# 04_ZYNQ_BANK0.net
KiCad netlist of a schematic drawn in Altium Designer
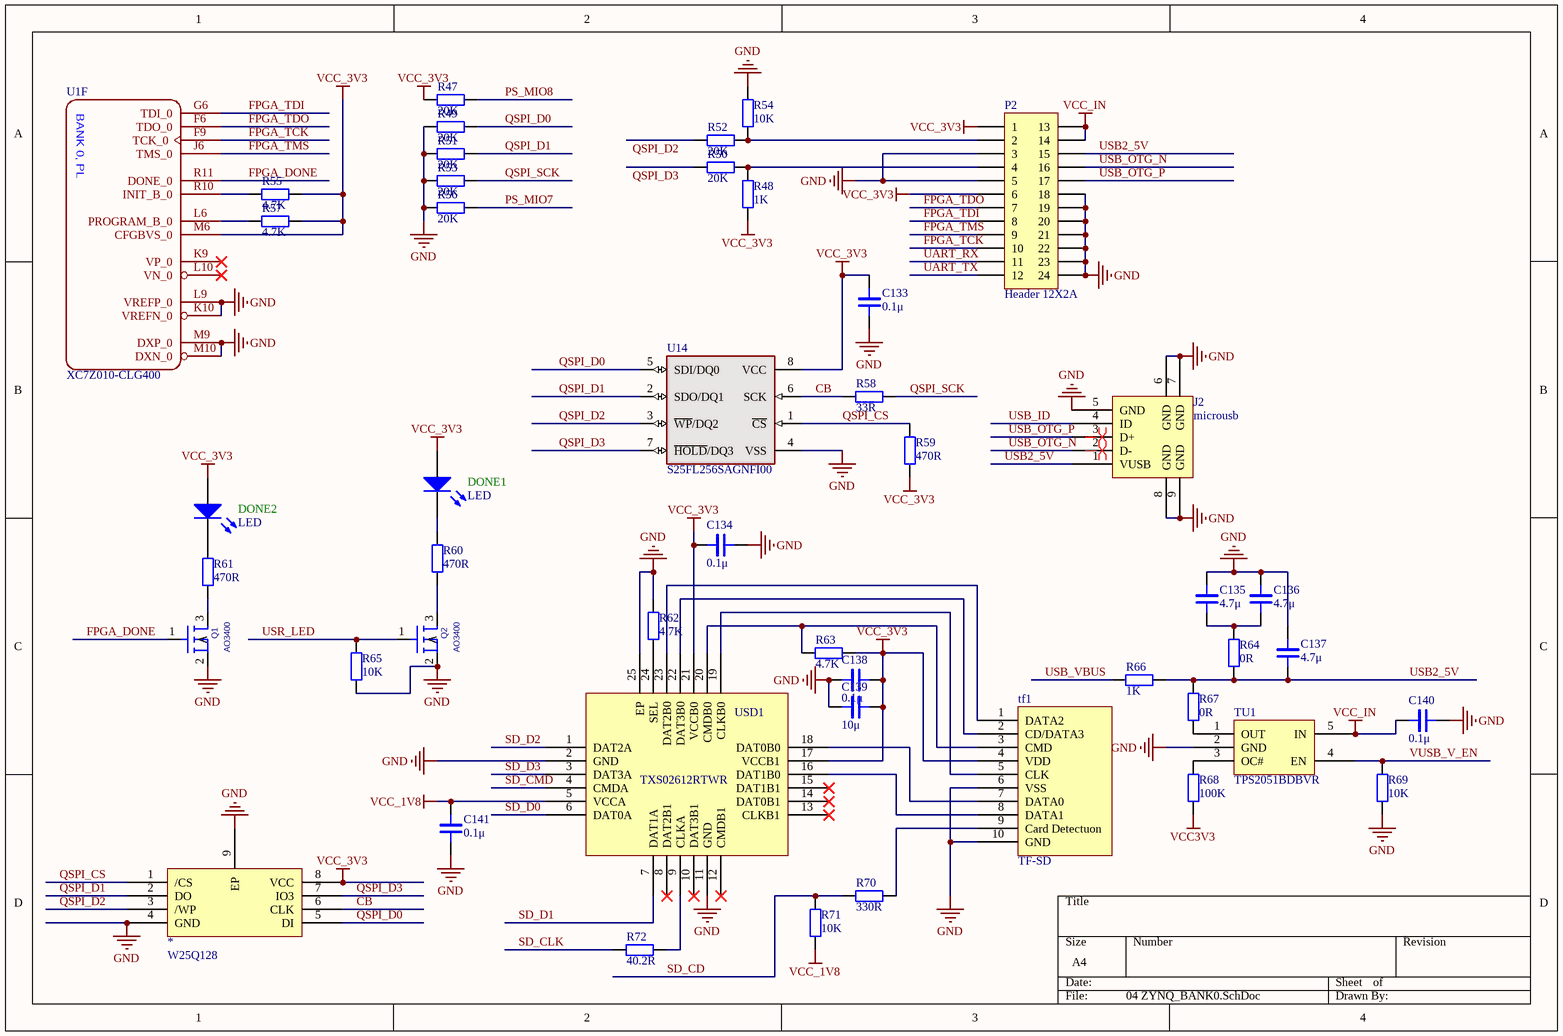
[diagram p0: 04 ZYNQ_BANK0.SchDoc]

(export (version "E")
  (design (tool "Eeschema 10.0.6"))
  (components
    (comp (ref "*") (value "W25Q128") (footprint "W25Q256") (libsource (lib "Schlib1") (part "W25Q128")))
    (comp (ref "C133")
      (value "0.1μ")
      (footprint "LC-0402_C")
      (description "Capacitor")
      (libsource (lib "DDR3_xc7z010-clg400") (part "CAP_2"))
    )
    (comp (ref "C134")
      (value "0.1μ")
      (footprint "LC-0402_C")
      (description "Capacitor")
      (libsource (lib "DDR3_xc7z010-clg400") (part "CAP_2"))
    )
    (comp (ref "C135")
      (value "4.7μ")
      (footprint "LC-0402_C")
      (description "Capacitor")
      (libsource (lib "DDR3_xc7z010-clg400") (part "CAP_2"))
    )
    (comp (ref "C136")
      (value "4.7μ")
      (footprint "LC-0402_C")
      (description "Capacitor")
      (libsource (lib "DDR3_xc7z010-clg400") (part "CAP_2"))
    )
    (comp (ref "C137")
      (value "4.7μ")
      (footprint "LC-0402_C")
      (description "Capacitor")
      (libsource (lib "DDR3_xc7z010-clg400") (part "CAP_2"))
    )
    (comp (ref "C138")
      (value "0.1μ")
      (footprint "LC-0402_C")
      (description "Capacitor")
      (libsource (lib "DDR3_xc7z010-clg400") (part "CAP_2"))
    )
    (comp (ref "C139")
      (value "10μ")
      (footprint "LC-0402_C")
      (description "Capacitor")
      (libsource (lib "DDR3_xc7z010-clg400") (part "CAP_2"))
    )
    (comp (ref "C140")
      (value "0.1μ")
      (footprint "LC-0402_C")
      (description "Capacitor")
      (libsource (lib "DDR3_xc7z010-clg400") (part "CAP_2"))
    )
    (comp (ref "C141")
      (value "0.1μ")
      (footprint "LC-0402_C")
      (description "Capacitor")
      (libsource (lib "DDR3_xc7z010-clg400") (part "CAP_2"))
    )
    (comp (ref "DONE1")
      (value "LED")
      (footprint "D0402")
      (description "Typical INFRARED GaAs LED")
      (fields (field (name "PUBLISHER") "Altium Limited"))
      (libsource (lib "Miscellaneous Devices") (part "LED0"))
    )
    (comp (ref "DONE2")
      (value "LED")
      (footprint "D0402")
      (description "Typical INFRARED GaAs LED")
      (fields (field (name "PUBLISHER") "Altium Limited"))
      (libsource (lib "Miscellaneous Devices") (part "LED0"))
    )
    (comp (ref "J2")
      (value "microusb")
      (footprint "micro usb")
      (libsource (lib "AD9363_ZYNQ_V2") (part "microusb"))
    )
    (comp (ref "P2")
      (value "Header 12X2A")
      (footprint "HDR2X12_CEN")
      (description "Header, 12-Pin, Dual row")
      (fields (field (name "PUBLISHER") "Altium Limited"))
      (libsource (lib "Miscellaneous Connectors") (part "Header 12X2A"))
    )
    (comp (ref "Q1") (value "AO3400") (footprint "NMOS") (libsource (lib "ZYNQ领航者底板") (part "AO3400")))
    (comp (ref "Q2") (value "AO3400") (footprint "NMOS") (libsource (lib "ZYNQ领航者底板") (part "AO3400")))
    (comp (ref "R47")
      (value "20K")
      (footprint "LC-0402_R")
      (description "Resistor")
      (libsource (lib "") (part "RES_2"))
    )
    (comp (ref "R48")
      (value "1K")
      (footprint "LC-0402_R")
      (description "Resistor")
      (libsource (lib "") (part "RES_3"))
    )
    (comp (ref "R49")
      (value "20K")
      (footprint "LC-0402_R")
      (description "Resistor")
      (libsource (lib "") (part "RES_2"))
    )
    (comp (ref "R50")
      (value "20K")
      (footprint "LC-0402_R")
      (description "Resistor")
      (libsource (lib "DDR3_xc7z010-clg400") (part "RES"))
    )
    (comp (ref "R51")
      (value "20K")
      (footprint "LC-0402_R")
      (description "Resistor")
      (libsource (lib "") (part "RES_2"))
    )
    (comp (ref "R52")
      (value "20K")
      (footprint "LC-0402_R")
      (description "Resistor")
      (libsource (lib "DDR3_xc7z010-clg400") (part "RES"))
    )
    (comp (ref "R53")
      (value "20K")
      (footprint "LC-0402_R")
      (description "Resistor")
      (libsource (lib "") (part "RES_2"))
    )
    (comp (ref "R54")
      (value "10K")
      (footprint "LC-0402_R")
      (description "Resistor")
      (libsource (lib "") (part "RES_3"))
    )
    (comp (ref "R55")
      (value "4.7K")
      (footprint "LC-0402_R")
      (description "Resistor")
      (libsource (lib "DDR3_xc7z010-clg400") (part "RES"))
    )
    (comp (ref "R56")
      (value "20K")
      (footprint "LC-0402_R")
      (description "Resistor")
      (libsource (lib "") (part "RES_2"))
    )
    (comp (ref "R57")
      (value "4.7K")
      (footprint "LC-0402_R")
      (description "Resistor")
      (libsource (lib "DDR3_xc7z010-clg400") (part "RES"))
    )
    (comp (ref "R58")
      (value "33R")
      (footprint "LC-0402_R")
      (description "Resistor")
      (libsource (lib "") (part "RES_2"))
    )
    (comp (ref "R59")
      (value "470R")
      (footprint "LC-0402_R")
      (description "Resistor")
      (libsource (lib "") (part "RES_1"))
    )
    (comp (ref "R60")
      (value "470R")
      (footprint "LC-0402_R")
      (description "Resistor")
      (libsource (lib "") (part "RES_3"))
    )
    (comp (ref "R61")
      (value "470R")
      (footprint "LC-0402_R")
      (description "Resistor")
      (libsource (lib "") (part "RES_3"))
    )
    (comp (ref "R62")
      (value "4.7K")
      (footprint "LC-0402_R")
      (description "Resistor")
      (libsource (lib "") (part "RES_1"))
    )
    (comp (ref "R63")
      (value "4.7K")
      (footprint "LC-0402_R")
      (description "Resistor")
      (libsource (lib "DDR3_xc7z010-clg400") (part "RES"))
    )
    (comp (ref "R64")
      (value "0R")
      (footprint "LC-0402_R")
      (description "Resistor")
      (libsource (lib "") (part "RES_1"))
    )
    (comp (ref "R65")
      (value "10K")
      (footprint "LC-0402_R")
      (description "Resistor")
      (libsource (lib "") (part "RES_1"))
    )
    (comp (ref "R66")
      (value "1K")
      (footprint "LC-0402_R")
      (description "Resistor")
      (libsource (lib "DDR3_xc7z010-clg400") (part "RES"))
    )
    (comp (ref "R67")
      (value "0R")
      (footprint "LC-0402_R")
      (description "Resistor")
      (libsource (lib "") (part "RES_1"))
    )
    (comp (ref "R68")
      (value "100K")
      (footprint "LC-0402_R")
      (description "Resistor")
      (libsource (lib "") (part "RES_1"))
    )
    (comp (ref "R69")
      (value "10K")
      (footprint "LC-0402_R")
      (description "Resistor")
      (libsource (lib "") (part "RES_1"))
    )
    (comp (ref "R70")
      (value "330R")
      (footprint "LC-0402_R")
      (description "Resistor")
      (libsource (lib "DDR3_xc7z010-clg400") (part "RES"))
    )
    (comp (ref "R71")
      (value "10K")
      (footprint "LC-0402_R")
      (description "Resistor")
      (libsource (lib "") (part "RES_1"))
    )
    (comp (ref "R72")
      (value "40.2R")
      (footprint "LC-0402_R")
      (description "Resistor")
      (libsource (lib "DDR3_xc7z010-clg400") (part "RES"))
    )
    (comp (ref "tf1") (value "TF-SD") (footprint "TF") (libsource (lib "PCB_Project") (part "TF-SD")))
    (comp (ref "TU1")
      (value "TPS2051BDBVR")
      (footprint "TPS2051BDBVR")
      (libsource (lib "Schlib1") (part "TPS2051BDBVR"))
    )
    (comp (ref "U1")
      (value "XC7Z010-CLG400")
      (footprint "CLG400-0.8")
      (libsource (lib "DDR3_xc7z010-clg400") (part "XC7Z010-CLG400"))
    )
    (comp (ref "U14")
      (value "S25FL256SAGNFI00")
      (footprint "MLP8")
      (description "Serial Flash Memory, 16Mbit, Low Voltage, 50MHz SPI Bus Interface")
      (fields (field (name "MANUFACTURER") "Spansion"))
      (libsource (lib "PCB_Project") (part "N25Q12-F8"))
    )
    (comp (ref "USD1")
      (value "TXS02612RTWR")
      (footprint "TXS02612RTWR")
      (libsource (lib "Schlib1") (part "TXS02612RTWR"))
    )
  )
  (nets
    (net (code "1") (name "/CB") (class "Default")
      (node (ref "*") (pin "6") (pinfunction "CLK_6") (pintype "passive"))
      (node (ref "R58") (pin "1") (pinfunction "1_1") (pintype "passive"))
      (node (ref "U14") (pin "6") (pinfunction "SCK_6") (pintype "input"))
    )
    (net (code "2") (name "/FPGA_DONE") (class "Default")
      (node (ref "Q1") (pin "1") (pinfunction "G_1") (pintype "passive"))
      (node (ref "U1") (pin "R11") (pinfunction "DONE_0_R11") (pintype "passive"))
    )
    (net (code "3") (name "/FPGA_TCK") (class "Default")
      (node (ref "P2") (pin "10") (pinfunction "10_10") (pintype "passive"))
      (node (ref "U1") (pin "F9") (pinfunction "TCK_0_F9") (pintype "passive"))
    )
    (net (code "4") (name "/FPGA_TDI") (class "Default")
      (node (ref "P2") (pin "8") (pinfunction "8_8") (pintype "passive"))
      (node (ref "U1") (pin "G6") (pinfunction "TDI_0_G6") (pintype "passive"))
    )
    (net (code "5") (name "/FPGA_TDO") (class "Default")
      (node (ref "P2") (pin "7") (pinfunction "7_7") (pintype "passive"))
      (node (ref "U1") (pin "F6") (pinfunction "TDO_0_F6") (pintype "passive"))
    )
    (net (code "6") (name "/FPGA_TMS") (class "Default")
      (node (ref "P2") (pin "9") (pinfunction "9_9") (pintype "passive"))
      (node (ref "U1") (pin "J6") (pinfunction "TMS_0_J6") (pintype "passive"))
    )
    (net (code "7") (name "/PS_MIO7") (class "Default")
      (node (ref "R56") (pin "2") (pinfunction "2_2") (pintype "passive"))
    )
    (net (code "8") (name "/PS_MIO8") (class "Default")
      (node (ref "R47") (pin "2") (pinfunction "2_2") (pintype "passive"))
    )
    (net (code "9") (name "/QSPI_CS") (class "Default")
      (node (ref "*") (pin "1") (pinfunction "/CS_1") (pintype "passive"))
      (node (ref "R59") (pin "1") (pinfunction "1_1") (pintype "passive"))
      (node (ref "U14") (pin "1") (pinfunction "~{CS}_1") (pintype "input"))
    )
    (net (code "10") (name "/QSPI_D0") (class "Default")
      (node (ref "*") (pin "5") (pinfunction "DI_5") (pintype "passive"))
      (node (ref "R49") (pin "2") (pinfunction "2_2") (pintype "passive"))
      (node (ref "U14") (pin "5") (pinfunction "SDI/DQ0_5") (pintype "bidirectional"))
    )
    (net (code "11") (name "/QSPI_D1") (class "Default")
      (node (ref "*") (pin "2") (pinfunction "DO_2") (pintype "passive"))
      (node (ref "R51") (pin "2") (pinfunction "2_2") (pintype "passive"))
      (node (ref "U14") (pin "2") (pinfunction "SDO/DQ1_2") (pintype "bidirectional"))
    )
    (net (code "12") (name "/QSPI_D2") (class "Default")
      (node (ref "*") (pin "3") (pinfunction "/WP_3") (pintype "passive"))
      (node (ref "R52") (pin "2") (pinfunction "2_2") (pintype "passive"))
      (node (ref "U14") (pin "3") (pinfunction "~{WP}/DQ2_3") (pintype "bidirectional"))
    )
    (net (code "13") (name "/QSPI_D3") (class "Default")
      (node (ref "*") (pin "7") (pinfunction "IO3_7") (pintype "passive"))
      (node (ref "R50") (pin "2") (pinfunction "2_2") (pintype "passive"))
      (node (ref "U14") (pin "7") (pinfunction "~{HOLD}/DQ3_7") (pintype "bidirectional"))
    )
    (net (code "14") (name "/QSPI_SCK") (class "Default")
      (node (ref "R53") (pin "2") (pinfunction "2_2") (pintype "passive"))
      (node (ref "R58") (pin "2") (pinfunction "2_2") (pintype "passive"))
    )
    (net (code "15") (name "/SD_CD") (class "Default")
      (node (ref "R70") (pin "2") (pinfunction "2_2") (pintype "passive"))
      (node (ref "R71") (pin "1") (pinfunction "1_1") (pintype "passive"))
    )
    (net (code "16") (name "/SD_CLK") (class "Default")
      (node (ref "R72") (pin "2") (pinfunction "2_2") (pintype "passive"))
    )
    (net (code "17") (name "/SD_CMD") (class "Default")
      (node (ref "USD1") (pin "4") (pinfunction "CMDA_4") (pintype "passive"))
    )
    (net (code "18") (name "/SD_D0") (class "Default")
      (node (ref "USD1") (pin "6") (pinfunction "DAT0A_6") (pintype "passive"))
    )
    (net (code "19") (name "/SD_D1") (class "Default")
      (node (ref "USD1") (pin "7") (pinfunction "DAT1A_7") (pintype "passive"))
    )
    (net (code "20") (name "/SD_D2") (class "Default")
      (node (ref "USD1") (pin "1") (pinfunction "DAT2A_1") (pintype "passive"))
    )
    (net (code "21") (name "/SD_D3") (class "Default")
      (node (ref "USD1") (pin "3") (pinfunction "DAT3A_3") (pintype "passive"))
    )
    (net (code "22") (name "/UART_RX") (class "Default")
      (node (ref "P2") (pin "11") (pinfunction "11_11") (pintype "passive"))
    )
    (net (code "23") (name "/UART_TX") (class "Default")
      (node (ref "P2") (pin "12") (pinfunction "12_12") (pintype "passive"))
    )
    (net (code "24") (name "/USB2_5V") (class "Default")
      (node (ref "C137") (pin "1") (pinfunction "1_1") (pintype "passive"))
      (node (ref "J2") (pin "1") (pinfunction "VUSB_1") (pintype "passive"))
      (node (ref "P2") (pin "15") (pinfunction "15_15") (pintype "passive"))
      (node (ref "R64") (pin "2") (pinfunction "2_2") (pintype "passive"))
      (node (ref "R66") (pin "1") (pinfunction "1_1") (pintype "passive"))
      (node (ref "R67") (pin "1") (pinfunction "1_1") (pintype "passive"))
    )
    (net (code "25") (name "/USB_ID") (class "Default")
      (node (ref "J2") (pin "4") (pinfunction "ID_4") (pintype "passive"))
    )
    (net (code "26") (name "/USB_OTG_N") (class "Default")
      (node (ref "J2") (pin "2") (pinfunction "D-_2") (pintype "passive"))
      (node (ref "P2") (pin "16") (pinfunction "16_16") (pintype "passive"))
    )
    (net (code "27") (name "/USB_OTG_P") (class "Default")
      (node (ref "J2") (pin "3") (pinfunction "D+_3") (pintype "passive"))
      (node (ref "P2") (pin "17") (pinfunction "17_17") (pintype "passive"))
    )
    (net (code "28") (name "/USB_VBUS") (class "Default")
      (node (ref "R66") (pin "2") (pinfunction "2_2") (pintype "passive"))
    )
    (net (code "29") (name "/USR_LED") (class "Default")
      (node (ref "Q2") (pin "1") (pinfunction "G_1") (pintype "passive"))
      (node (ref "R65") (pin "1") (pinfunction "1_1") (pintype "passive"))
    )
    (net (code "30") (name "/VUSB_V_EN") (class "Default")
      (node (ref "R69") (pin "1") (pinfunction "1_1") (pintype "passive"))
      (node (ref "TU1") (pin "4") (pinfunction "EN_4") (pintype "passive"))
    )
    (net (code "31") (name "GND") (class "Default")
      (node (ref "*") (pin "4") (pinfunction "GND_4") (pintype "passive"))
      (node (ref "*") (pin "9") (pinfunction "EP_9") (pintype "passive"))
      (node (ref "C133") (pin "2") (pinfunction "2_2") (pintype "passive"))
      (node (ref "C134") (pin "2") (pinfunction "2_2") (pintype "passive"))
      (node (ref "C135") (pin "2") (pinfunction "2_2") (pintype "passive"))
      (node (ref "C136") (pin "2") (pinfunction "2_2") (pintype "passive"))
      (node (ref "C137") (pin "2") (pinfunction "2_2") (pintype "passive"))
      (node (ref "C138") (pin "2") (pinfunction "2_2") (pintype "passive"))
      (node (ref "C139") (pin "2") (pinfunction "2_2") (pintype "passive"))
      (node (ref "C140") (pin "1") (pinfunction "1_1") (pintype "passive"))
      (node (ref "C141") (pin "2") (pinfunction "2_2") (pintype "passive"))
      (node (ref "J2") (pin "5") (pinfunction "GND_5") (pintype "passive"))
      (node (ref "J2") (pin "6") (pinfunction "GND_6") (pintype "passive"))
      (node (ref "J2") (pin "7") (pinfunction "GND_7") (pintype "passive"))
      (node (ref "J2") (pin "8") (pinfunction "GND_8") (pintype "passive"))
      (node (ref "J2") (pin "9") (pinfunction "GND_9") (pintype "passive"))
      (node (ref "P2") (pin "18") (pinfunction "18_18") (pintype "passive"))
      (node (ref "P2") (pin "19") (pinfunction "19_19") (pintype "passive"))
      (node (ref "P2") (pin "20") (pinfunction "20_20") (pintype "passive"))
      (node (ref "P2") (pin "21") (pinfunction "21_21") (pintype "passive"))
      (node (ref "P2") (pin "22") (pinfunction "22_22") (pintype "passive"))
      (node (ref "P2") (pin "23") (pinfunction "23_23") (pintype "passive"))
      (node (ref "P2") (pin "24") (pinfunction "24_24") (pintype "passive"))
      (node (ref "P2") (pin "3") (pinfunction "3_3") (pintype "passive"))
      (node (ref "P2") (pin "5") (pinfunction "5_5") (pintype "passive"))
      (node (ref "Q1") (pin "2") (pinfunction "S_2") (pintype "passive"))
      (node (ref "Q2") (pin "2") (pinfunction "S_2") (pintype "passive"))
      (node (ref "R49") (pin "1") (pinfunction "1_1") (pintype "passive"))
      (node (ref "R51") (pin "1") (pinfunction "1_1") (pintype "passive"))
      (node (ref "R53") (pin "1") (pinfunction "1_1") (pintype "passive"))
      (node (ref "R54") (pin "2") (pinfunction "2_2") (pintype "passive"))
      (node (ref "R56") (pin "1") (pinfunction "1_1") (pintype "passive"))
      (node (ref "R62") (pin "1") (pinfunction "1_1") (pintype "passive"))
      (node (ref "R65") (pin "2") (pinfunction "2_2") (pintype "passive"))
      (node (ref "R69") (pin "2") (pinfunction "2_2") (pintype "passive"))
      (node (ref "TU1") (pin "2") (pinfunction "GND_2") (pintype "passive"))
      (node (ref "U1") (pin "K10") (pinfunction "VREFN_0_K10") (pintype "passive"))
      (node (ref "U1") (pin "L9") (pinfunction "VREFP_0_L9") (pintype "passive"))
      (node (ref "U1") (pin "M10") (pinfunction "DXN_0_M10") (pintype "passive"))
      (node (ref "U1") (pin "M9") (pinfunction "DXP_0_M9") (pintype "passive"))
      (node (ref "U14") (pin "4") (pinfunction "VSS_4") (pintype "power_in"))
      (node (ref "USD1") (pin "11") (pinfunction "GND_11") (pintype "passive"))
      (node (ref "USD1") (pin "2") (pinfunction "GND_2") (pintype "passive"))
      (node (ref "USD1") (pin "25") (pinfunction "EP_25") (pintype "passive"))
      (node (ref "tf1") (pin "10") (pinfunction "GND_10") (pintype "passive"))
      (node (ref "tf1") (pin "6") (pinfunction "VSS_6") (pintype "passive"))
    )
    (net (code "32") (name "Net-(C135-Pad1)") (class "Default")
      (node (ref "C135") (pin "1") (pinfunction "1_1") (pintype "passive"))
      (node (ref "C136") (pin "1") (pinfunction "1_1") (pintype "passive"))
      (node (ref "R64") (pin "1") (pinfunction "1_1") (pintype "passive"))
    )
    (net (code "33") (name "Net-(DONE1-K)") (class "Default")
      (node (ref "DONE1") (pin "2") (pinfunction "K_2") (pintype "passive"))
      (node (ref "R60") (pin "2") (pinfunction "2_2") (pintype "passive"))
    )
    (net (code "34") (name "Net-(DONE2-K)") (class "Default")
      (node (ref "DONE2") (pin "2") (pinfunction "K_2") (pintype "passive"))
      (node (ref "R61") (pin "2") (pinfunction "2_2") (pintype "passive"))
    )
    (net (code "35") (name "Net-(P2-Pad2)") (class "Default")
      (node (ref "P2") (pin "2") (pinfunction "2_2") (pintype "passive"))
      (node (ref "R52") (pin "1") (pinfunction "1_1") (pintype "passive"))
      (node (ref "R54") (pin "1") (pinfunction "1_1") (pintype "passive"))
    )
    (net (code "36") (name "Net-(P2-Pad4)") (class "Default")
      (node (ref "P2") (pin "4") (pinfunction "4_4") (pintype "passive"))
      (node (ref "R48") (pin "2") (pinfunction "2_2") (pintype "passive"))
      (node (ref "R50") (pin "1") (pinfunction "1_1") (pintype "passive"))
    )
    (net (code "37") (name "Net-(Q1-D)") (class "Default")
      (node (ref "Q1") (pin "3") (pinfunction "D_3") (pintype "passive"))
      (node (ref "R61") (pin "1") (pinfunction "1_1") (pintype "passive"))
    )
    (net (code "38") (name "Net-(Q2-D)") (class "Default")
      (node (ref "Q2") (pin "3") (pinfunction "D_3") (pintype "passive"))
      (node (ref "R60") (pin "1") (pinfunction "1_1") (pintype "passive"))
    )
    (net (code "39") (name "Net-(TU1-OC#)") (class "Default")
      (node (ref "R68") (pin "1") (pinfunction "1_1") (pintype "passive"))
      (node (ref "TU1") (pin "3") (pinfunction "OC#_3") (pintype "passive"))
    )
    (net (code "40") (name "Net-(TU1-OUT)") (class "Default")
      (node (ref "R67") (pin "2") (pinfunction "2_2") (pintype "passive"))
      (node (ref "TU1") (pin "1") (pinfunction "OUT_1") (pintype "passive"))
    )
    (net (code "41") (name "Net-(U1F-INIT_B_0)") (class "Default")
      (node (ref "R55") (pin "2") (pinfunction "2_2") (pintype "passive"))
      (node (ref "U1") (pin "R10") (pinfunction "INIT_B_0_R10") (pintype "passive"))
    )
    (net (code "42") (name "Net-(U1F-PROGRAM_B_0)") (class "Default")
      (node (ref "R57") (pin "2") (pinfunction "2_2") (pintype "passive"))
      (node (ref "U1") (pin "L6") (pinfunction "PROGRAM_B_0_L6") (pintype "passive"))
    )
    (net (code "43") (name "Net-(USD1-CLKA)") (class "Default")
      (node (ref "R72") (pin "1") (pinfunction "1_1") (pintype "passive"))
      (node (ref "USD1") (pin "9") (pinfunction "CLKA_9") (pintype "passive"))
    )
    (net (code "44") (name "Net-(USD1-CLKB0)") (class "Default")
      (node (ref "USD1") (pin "19") (pinfunction "CLKB0_19") (pintype "passive"))
      (node (ref "tf1") (pin "5") (pinfunction "CLK_5") (pintype "passive"))
    )
    (net (code "45") (name "Net-(USD1-CMDB0)") (class "Default")
      (node (ref "R63") (pin "2") (pinfunction "2_2") (pintype "passive"))
      (node (ref "USD1") (pin "20") (pinfunction "CMDB0_20") (pintype "passive"))
      (node (ref "tf1") (pin "3") (pinfunction "CMD_3") (pintype "passive"))
    )
    (net (code "46") (name "Net-(USD1-DAT0B0)") (class "Default")
      (node (ref "USD1") (pin "18") (pinfunction "DAT0B0_18") (pintype "passive"))
      (node (ref "tf1") (pin "7") (pinfunction "DATA0_7") (pintype "passive"))
    )
    (net (code "47") (name "Net-(USD1-DAT1B0)") (class "Default")
      (node (ref "USD1") (pin "16") (pinfunction "DAT1B0_16") (pintype "passive"))
      (node (ref "tf1") (pin "8") (pinfunction "DATA1_8") (pintype "passive"))
    )
    (net (code "48") (name "Net-(USD1-DAT2B0)") (class "Default")
      (node (ref "USD1") (pin "23") (pinfunction "DAT2B0_23") (pintype "passive"))
      (node (ref "tf1") (pin "1") (pinfunction "DATA2_1") (pintype "passive"))
    )
    (net (code "49") (name "Net-(USD1-DAT3B0)") (class "Default")
      (node (ref "USD1") (pin "22") (pinfunction "DAT3B0_22") (pintype "passive"))
      (node (ref "tf1") (pin "2") (pinfunction "CD/DATA3_2") (pintype "passive"))
    )
    (net (code "50") (name "Net-(USD1-SEL)") (class "Default")
      (node (ref "R62") (pin "2") (pinfunction "2_2") (pintype "passive"))
      (node (ref "USD1") (pin "24") (pinfunction "SEL_24") (pintype "passive"))
    )
    (net (code "51") (name "Net-(tf1-Card_Detectuon)") (class "Default")
      (node (ref "R70") (pin "1") (pinfunction "1_1") (pintype "passive"))
      (node (ref "tf1") (pin "9") (pinfunction "Card_Detectuon_9") (pintype "passive"))
    )
    (net (code "52") (name "VCC3V3") (class "Default")
      (node (ref "R68") (pin "2") (pinfunction "2_2") (pintype "passive"))
    )
    (net (code "53") (name "VCC_1V8") (class "Default")
      (node (ref "C141") (pin "1") (pinfunction "1_1") (pintype "passive"))
      (node (ref "R71") (pin "2") (pinfunction "2_2") (pintype "passive"))
      (node (ref "USD1") (pin "5") (pinfunction "VCCA_5") (pintype "passive"))
    )
    (net (code "54") (name "VCC_3V3") (class "Default")
      (node (ref "*") (pin "8") (pinfunction "VCC_8") (pintype "passive"))
      (node (ref "C133") (pin "1") (pinfunction "1_1") (pintype "passive"))
      (node (ref "C134") (pin "1") (pinfunction "1_1") (pintype "passive"))
      (node (ref "C138") (pin "1") (pinfunction "1_1") (pintype "passive"))
      (node (ref "C139") (pin "1") (pinfunction "1_1") (pintype "passive"))
      (node (ref "DONE1") (pin "1") (pinfunction "A_1") (pintype "passive"))
      (node (ref "DONE2") (pin "1") (pinfunction "A_1") (pintype "passive"))
      (node (ref "P2") (pin "1") (pinfunction "1_1") (pintype "passive"))
      (node (ref "P2") (pin "6") (pinfunction "6_6") (pintype "passive"))
      (node (ref "R47") (pin "1") (pinfunction "1_1") (pintype "passive"))
      (node (ref "R48") (pin "1") (pinfunction "1_1") (pintype "passive"))
      (node (ref "R55") (pin "1") (pinfunction "1_1") (pintype "passive"))
      (node (ref "R57") (pin "1") (pinfunction "1_1") (pintype "passive"))
      (node (ref "R59") (pin "2") (pinfunction "2_2") (pintype "passive"))
      (node (ref "R63") (pin "1") (pinfunction "1_1") (pintype "passive"))
      (node (ref "U1") (pin "M6") (pinfunction "CFGBVS_0_M6") (pintype "passive"))
      (node (ref "U14") (pin "8") (pinfunction "VCC_8") (pintype "power_in"))
      (node (ref "USD1") (pin "17") (pinfunction "VCCB1_17") (pintype "passive"))
      (node (ref "USD1") (pin "21") (pinfunction "VCCB0_21") (pintype "passive"))
      (node (ref "tf1") (pin "4") (pinfunction "VDD_4") (pintype "passive"))
    )
    (net (code "55") (name "VCC_IN") (class "Default")
      (node (ref "C140") (pin "2") (pinfunction "2_2") (pintype "passive"))
      (node (ref "P2") (pin "13") (pinfunction "13_13") (pintype "passive"))
      (node (ref "P2") (pin "14") (pinfunction "14_14") (pintype "passive"))
      (node (ref "TU1") (pin "5") (pinfunction "IN_5") (pintype "passive"))
    )
    (net (code "56") (name "unconnected-(U1F-VN_0-PadL10)") (class "Default")
      (node (ref "U1") (pin "L10") (pinfunction "VN_0_L10") (pintype "passive+no_connect"))
    )
    (net (code "57") (name "unconnected-(U1F-VP_0-PadK9)") (class "Default")
      (node (ref "U1") (pin "K9") (pinfunction "VP_0_K9") (pintype "passive+no_connect"))
    )
    (net (code "58") (name "unconnected-(USD1-CLKB1-Pad13)") (class "Default")
      (node (ref "USD1") (pin "13") (pinfunction "CLKB1_13") (pintype "passive+no_connect"))
    )
    (net (code "59") (name "unconnected-(USD1-CMDB1-Pad12)") (class "Default")
      (node (ref "USD1") (pin "12") (pinfunction "CMDB1_12") (pintype "passive+no_connect"))
    )
    (net (code "60") (name "unconnected-(USD1-DAT0B1-Pad14)") (class "Default")
      (node (ref "USD1") (pin "14") (pinfunction "DAT0B1_14") (pintype "passive+no_connect"))
    )
    (net (code "61") (name "unconnected-(USD1-DAT1B1-Pad15)") (class "Default")
      (node (ref "USD1") (pin "15") (pinfunction "DAT1B1_15") (pintype "passive+no_connect"))
    )
    (net (code "62") (name "unconnected-(USD1-DAT2B1-Pad8)") (class "Default")
      (node (ref "USD1") (pin "8") (pinfunction "DAT2B1_8") (pintype "passive+no_connect"))
    )
    (net (code "63") (name "unconnected-(USD1-DAT3B1-Pad10)") (class "Default")
      (node (ref "USD1") (pin "10") (pinfunction "DAT3B1_10") (pintype "passive+no_connect"))
    )
  )
)
